# Sheet1.net
KiCad netlist of a schematic drawn in Altium Designer
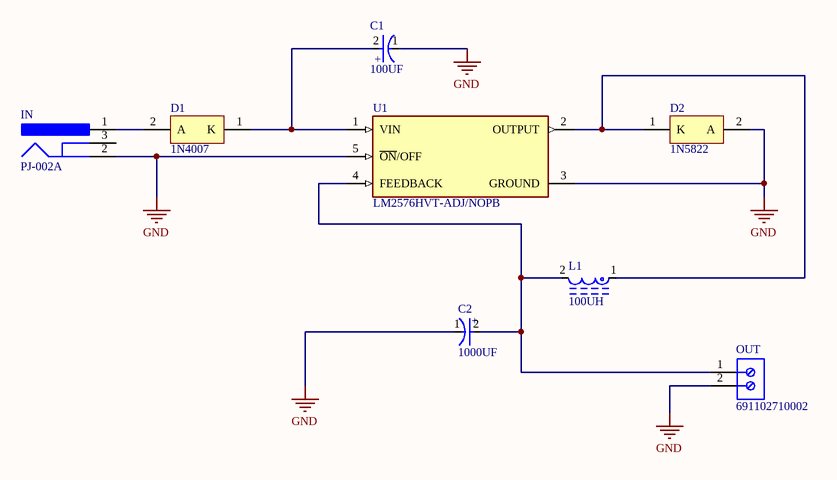
[diagram p0: Sheet1.SchDoc]

(export (version "E")
  (design (tool "Eeschema 10.0.6"))
  (components
    (comp (ref "C1")
      (value "100UF")
      (footprint "FP-RAD-TH-D_12_5_0_5-L_20-MFG")
      (description "Aluminum Electrolytic Capacitors (Radial Lead Type) 1000uF ±20% 25V")
      (fields (field (name "TOLERANCE") "20%") (field (name "VOLTAGE") "25V"))
      (libsource (lib "Altium Content Vault") (part "a00bbbee19879c290e62620ae7e47b1"))
    )
    (comp (ref "C2")
      (value "1000UF")
      (footprint "FP-RAD-TH-D_12_5_0_5-L_20-MFG")
      (description "Aluminum Electrolytic Capacitors (Radial Lead Type) 1000uF ±20% 25V")
      (fields (field (name "TOLERANCE") "20%") (field (name "VOLTAGE") "25V"))
      (libsource (lib "Altium Content Vault") (part "a00bbbee19879c290e62620ae7e47b1"))
    )
    (comp (ref "D1")
      (value "1N4007")
      (footprint "ONSC-AXIAL_LEAD-2-59-10_P")
      (description "Standard Recovery Rectifier, 2-Pin Axial_Lead, Pb-Free, Bulk Bag")
      (fields (field (name "MANUFACTURER") "On Semiconductor"))
      (libsource (lib "Altium Content Vault") (part "ONSC-D-K1A2-2_A"))
    )
    (comp (ref "D2")
      (value "1N5822")
      (footprint "ONSC-AXIAL_LEAD-2-267-05_V")
      (description "Rectifier, 2-Pin Axial_Lead, Bulk Bag")
      (fields (field (name "MANUFACTURER") "On Semiconductor"))
      (libsource (lib "") (part "ONSC-D-K1A2-2_A_1"))
    )
    (comp (ref "IN")
      (value "PJ-002A")
      (footprint "CUI-PJ-002A_V")
      (fields (field (name "MANUFACTURER") "CUIInc."))
      (libsource (lib "Altium Content Vault") (part "JACK-2CD3-RN_B"))
    )
    (comp (ref "L1")
      (value "100UH")
      (footprint "FP-RLB0914-MFG")
      (description "FIXED IND 100UH 1A 280 MOHM TH")
      (fields (field (name "TOLERANCE") "10%"))
      (libsource (lib "Altium Content Vault") (part "3970584d6af639339bee001af023dc2"))
    )
    (comp (ref "OUT")
      (value "691102710002")
      (footprint "691102710002")
      (description "Series 102 - 5.00 mm Horizontal Entry Modular with Pressure Clamp WR-TBL, 2 pin")
      (fields (field (name "MANUFACTURER") "Wurth Elektronik") (field (name "PUBLISHER") "WurthElektronik"))
      (libsource (lib "Altium Content Vault") (part "WE-CN-1P-F-TB2"))
    )
    (comp (ref "U1")
      (value "LM2576HVT-ADJ/NOPB")
      (footprint "FP-KC0005A-MFG")
      (description "Conv DC-DC Single Inv/Step Down 4V to 60V 5-Pin(5+Tab) TO-220")
      (fields
        (field (name "OCTOPART") "https://octopart.com/lm2576hvt-adj%2Fnopb-texas+instruments-24812812")
      )
      (libsource (lib "Altium Content Vault") (part "af72ba88e9d39e26ffdd0364993ec9b"))
    )
  )
  (nets
    (net (code "1") (name "GND") (class "Default")
      (node (ref "C1") (pin "1") (pinfunction "C_1") (pintype "passive"))
      (node (ref "C2") (pin "1") (pinfunction "C_1") (pintype "passive"))
      (node (ref "D2") (pin "2") (pinfunction "A_2") (pintype "passive"))
      (node (ref "IN") (pin "2") (pinfunction "2_2") (pintype "passive"))
      (node (ref "OUT") (pin "2") (pinfunction "2_2") (pintype "passive"))
      (node (ref "U1") (pin "3") (pinfunction "GROUND_3") (pintype "power_in"))
      (node (ref "U1") (pin "5") (pinfunction "~{ON}/OFF_5") (pintype "input"))
    )
    (net (code "2") (name "Net-(C1-A)") (class "Default")
      (node (ref "C1") (pin "2") (pinfunction "A_2") (pintype "passive"))
      (node (ref "D1") (pin "1") (pinfunction "K_1") (pintype "passive"))
      (node (ref "U1") (pin "1") (pinfunction "VIN_1") (pintype "input"))
    )
    (net (code "3") (name "Net-(C2-A)") (class "Default")
      (node (ref "C2") (pin "2") (pinfunction "A_2") (pintype "passive"))
      (node (ref "L1") (pin "2") (pinfunction "2_2") (pintype "passive"))
      (node (ref "OUT") (pin "1") (pinfunction "1_1") (pintype "passive"))
      (node (ref "U1") (pin "4") (pinfunction "FEEDBACK_4") (pintype "input"))
    )
    (net (code "4") (name "Net-(D1-A)") (class "Default")
      (node (ref "D1") (pin "2") (pinfunction "A_2") (pintype "passive"))
      (node (ref "IN") (pin "1") (pinfunction "1_1") (pintype "passive"))
    )
    (net (code "5") (name "Net-(D2-K)") (class "Default")
      (node (ref "D2") (pin "1") (pinfunction "K_1") (pintype "passive"))
      (node (ref "L1") (pin "1") (pinfunction "1_1") (pintype "passive"))
      (node (ref "U1") (pin "2") (pinfunction "OUTPUT_2") (pintype "output"))
    )
    (net (code "6") (name "unconnected-(IN-Pad3)") (class "Default")
      (node (ref "IN") (pin "3") (pinfunction "3_3") (pintype "passive"))
    )
  )
)
